# v001.net
KiCad netlist of a schematic drawn in EAGLE
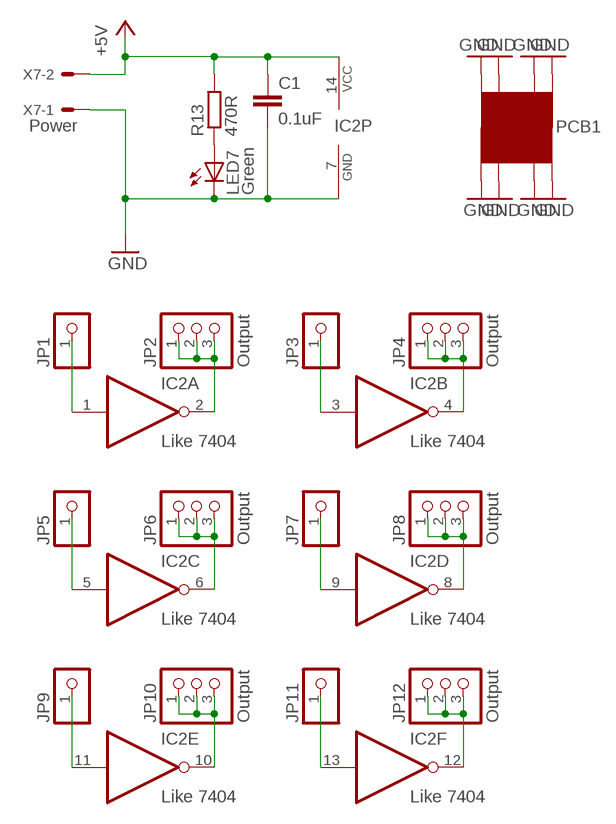
[diagram p0: schematic, sheet 1]

(export (version "E")
  (design (tool "Eeschema 10.0.6"))
  (components
    (comp (ref "C1")
      (value "0.1uF")
      (footprint "eagle-import:C050-024X044")
      (libsource (lib "eagle-import") (part "C-EU050-024X044"))
    )
    (comp (ref "IC2")
      (value "Like 7404")
      (footprint "eagle-import:DIL14")
      (libsource (lib "eagle-import") (part "7404NALS"))
    )
    (comp (ref "JP1")
      (value "PINHD-1X1")
      (footprint "eagle-import:1X01")
      (libsource (lib "eagle-import") (part "PINHD-1X1"))
    )
    (comp (ref "JP2")
      (value "Output")
      (footprint "eagle-import:1X03")
      (libsource (lib "eagle-import") (part "PINHD-1X3"))
    )
    (comp (ref "JP3")
      (value "PINHD-1X1")
      (footprint "eagle-import:1X01")
      (libsource (lib "eagle-import") (part "PINHD-1X1"))
    )
    (comp (ref "JP4")
      (value "Output")
      (footprint "eagle-import:1X03")
      (libsource (lib "eagle-import") (part "PINHD-1X3"))
    )
    (comp (ref "JP5")
      (value "PINHD-1X1")
      (footprint "eagle-import:1X01")
      (libsource (lib "eagle-import") (part "PINHD-1X1"))
    )
    (comp (ref "JP6")
      (value "Output")
      (footprint "eagle-import:1X03")
      (libsource (lib "eagle-import") (part "PINHD-1X3"))
    )
    (comp (ref "JP7")
      (value "PINHD-1X1")
      (footprint "eagle-import:1X01")
      (libsource (lib "eagle-import") (part "PINHD-1X1"))
    )
    (comp (ref "JP8")
      (value "Output")
      (footprint "eagle-import:1X03")
      (libsource (lib "eagle-import") (part "PINHD-1X3"))
    )
    (comp (ref "JP9")
      (value "PINHD-1X1")
      (footprint "eagle-import:1X01")
      (libsource (lib "eagle-import") (part "PINHD-1X1"))
    )
    (comp (ref "JP10")
      (value "Output")
      (footprint "eagle-import:1X03")
      (libsource (lib "eagle-import") (part "PINHD-1X3"))
    )
    (comp (ref "JP11")
      (value "PINHD-1X1")
      (footprint "eagle-import:1X01")
      (libsource (lib "eagle-import") (part "PINHD-1X1"))
    )
    (comp (ref "JP12")
      (value "Output")
      (footprint "eagle-import:1X03")
      (libsource (lib "eagle-import") (part "PINHD-1X3"))
    )
    (comp (ref "LED7")
      (value "Green")
      (footprint "eagle-import:LED3MM")
      (libsource (lib "eagle-import") (part "LED3MM"))
    )
    (comp (ref "PCB1")
      (value "PCB05X05")
      (footprint "eagle-import:PCB_05X05")
      (libsource (lib "eagle-import") (part "PCB05X05"))
    )
    (comp (ref "R13")
      (value "470R")
      (footprint "eagle-import:0204_7")
      (libsource (lib "eagle-import") (part "R-EU_0204/7"))
    )
    (comp (ref "X7")
      (value "Power")
      (footprint "eagle-import:6410-02")
      (libsource (lib "eagle-import") (part "22-?-0227-2021"))
    )
  )
  (nets
    (net (code "1") (name "+5V") (class "Default")
      (node (ref "C1") (pin "1") (pinfunction "1_1") (pintype "passive"))
      (node (ref "IC2") (pin "14") (pinfunction "VCC_14") (pintype "power_in"))
      (node (ref "R13") (pin "2") (pinfunction "2_2") (pintype "passive"))
      (node (ref "X7") (pin "2") (pinfunction "S_2") (pintype "passive"))
    )
    (net (code "2") (name "GND") (class "Default")
      (node (ref "C1") (pin "2") (pinfunction "2_2") (pintype "passive"))
      (node (ref "IC2") (pin "7") (pinfunction "GND_7") (pintype "power_in"))
      (node (ref "LED7") (pin "K") (pinfunction "C_K") (pintype "passive"))
      (node (ref "PCB1") (pin "GND@1") (pinfunction "GND_GND@1") (pintype "bidirectional"))
      (node (ref "PCB1") (pin "GND@2") (pinfunction "GND_GND@2") (pintype "bidirectional"))
      (node (ref "PCB1") (pin "GND@3") (pinfunction "GND_GND@3") (pintype "bidirectional"))
      (node (ref "PCB1") (pin "GND@4") (pinfunction "GND_GND@4") (pintype "bidirectional"))
      (node (ref "PCB1") (pin "GND@5") (pinfunction "GND_GND@5") (pintype "bidirectional"))
      (node (ref "PCB1") (pin "GND@6") (pinfunction "GND_GND@6") (pintype "bidirectional"))
      (node (ref "PCB1") (pin "GND@7") (pinfunction "GND_GND@7") (pintype "bidirectional"))
      (node (ref "PCB1") (pin "GND@8") (pinfunction "GND_GND@8") (pintype "bidirectional"))
      (node (ref "X7") (pin "1") (pinfunction "S_1") (pintype "passive"))
    )
    (net (code "3") (name "Net-(IC2A-I)") (class "Default")
      (node (ref "IC2") (pin "1") (pinfunction "I_1") (pintype "input"))
      (node (ref "JP1") (pin "1") (pinfunction "1_1") (pintype "passive"))
    )
    (net (code "4") (name "Net-(IC2A-O)") (class "Default")
      (node (ref "IC2") (pin "2") (pinfunction "O_2") (pintype "output"))
      (node (ref "JP2") (pin "1") (pinfunction "1_1") (pintype "passive"))
      (node (ref "JP2") (pin "2") (pinfunction "2_2") (pintype "passive"))
      (node (ref "JP2") (pin "3") (pinfunction "3_3") (pintype "passive"))
    )
    (net (code "5") (name "Net-(IC2B-I)") (class "Default")
      (node (ref "IC2") (pin "3") (pinfunction "I_3") (pintype "input"))
      (node (ref "JP3") (pin "1") (pinfunction "1_1") (pintype "passive"))
    )
    (net (code "6") (name "Net-(IC2B-O)") (class "Default")
      (node (ref "IC2") (pin "4") (pinfunction "O_4") (pintype "output"))
      (node (ref "JP4") (pin "1") (pinfunction "1_1") (pintype "passive"))
      (node (ref "JP4") (pin "2") (pinfunction "2_2") (pintype "passive"))
      (node (ref "JP4") (pin "3") (pinfunction "3_3") (pintype "passive"))
    )
    (net (code "7") (name "Net-(IC2C-I)") (class "Default")
      (node (ref "IC2") (pin "5") (pinfunction "I_5") (pintype "input"))
      (node (ref "JP5") (pin "1") (pinfunction "1_1") (pintype "passive"))
    )
    (net (code "8") (name "Net-(IC2C-O)") (class "Default")
      (node (ref "IC2") (pin "6") (pinfunction "O_6") (pintype "output"))
      (node (ref "JP6") (pin "1") (pinfunction "1_1") (pintype "passive"))
      (node (ref "JP6") (pin "2") (pinfunction "2_2") (pintype "passive"))
      (node (ref "JP6") (pin "3") (pinfunction "3_3") (pintype "passive"))
    )
    (net (code "9") (name "Net-(IC2D-I)") (class "Default")
      (node (ref "IC2") (pin "9") (pinfunction "I_9") (pintype "input"))
      (node (ref "JP7") (pin "1") (pinfunction "1_1") (pintype "passive"))
    )
    (net (code "10") (name "Net-(IC2D-O)") (class "Default")
      (node (ref "IC2") (pin "8") (pinfunction "O_8") (pintype "output"))
      (node (ref "JP8") (pin "1") (pinfunction "1_1") (pintype "passive"))
      (node (ref "JP8") (pin "2") (pinfunction "2_2") (pintype "passive"))
      (node (ref "JP8") (pin "3") (pinfunction "3_3") (pintype "passive"))
    )
    (net (code "11") (name "Net-(IC2E-I)") (class "Default")
      (node (ref "IC2") (pin "11") (pinfunction "I_11") (pintype "input"))
      (node (ref "JP9") (pin "1") (pinfunction "1_1") (pintype "passive"))
    )
    (net (code "12") (name "Net-(IC2E-O)") (class "Default")
      (node (ref "IC2") (pin "10") (pinfunction "O_10") (pintype "output"))
      (node (ref "JP10") (pin "1") (pinfunction "1_1") (pintype "passive"))
      (node (ref "JP10") (pin "2") (pinfunction "2_2") (pintype "passive"))
      (node (ref "JP10") (pin "3") (pinfunction "3_3") (pintype "passive"))
    )
    (net (code "13") (name "Net-(IC2F-I)") (class "Default")
      (node (ref "IC2") (pin "13") (pinfunction "I_13") (pintype "input"))
      (node (ref "JP11") (pin "1") (pinfunction "1_1") (pintype "passive"))
    )
    (net (code "14") (name "Net-(IC2F-O)") (class "Default")
      (node (ref "IC2") (pin "12") (pinfunction "O_12") (pintype "output"))
      (node (ref "JP12") (pin "1") (pinfunction "1_1") (pintype "passive"))
      (node (ref "JP12") (pin "2") (pinfunction "2_2") (pintype "passive"))
      (node (ref "JP12") (pin "3") (pinfunction "3_3") (pintype "passive"))
    )
    (net (code "15") (name "Net-(LED7-PadA)") (class "Default")
      (node (ref "LED7") (pin "A") (pinfunction "A_A") (pintype "passive"))
      (node (ref "R13") (pin "1") (pinfunction "1_1") (pintype "passive"))
    )
  )
)
